# 4-PPS.net
KiCad netlist of a schematic drawn in Altium Designer
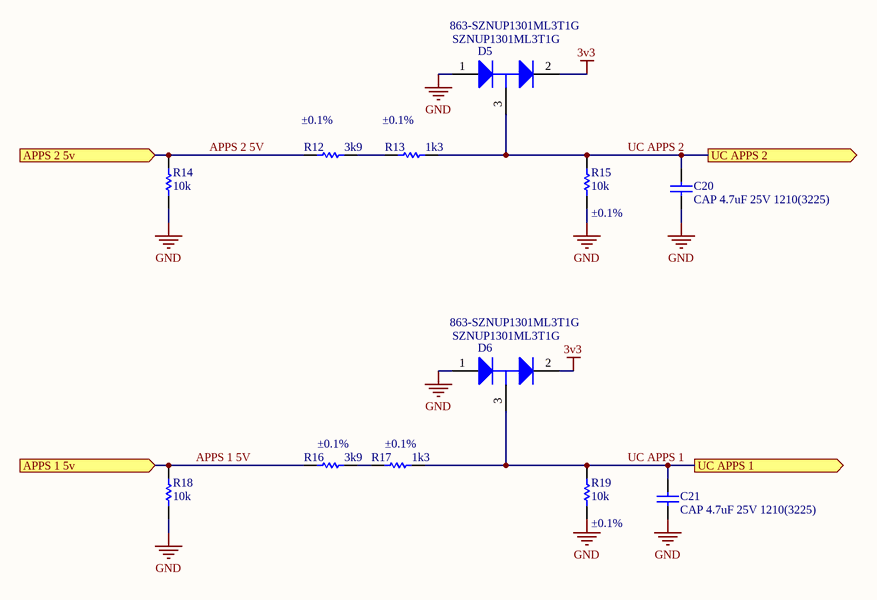
[diagram p0: 4-PPS.SchDoc]

(export (version "E")
  (design (tool "Eeschema 10.0.6"))
  (components
    (comp (ref "C20")
      (value "CAP 4.7uF 25V 1210(3225)")
      (footprint "CAPC1210(3225)220_M")
      (description "CAP 4.7uF 25V ±10% 1210 (3225 Metric) Thickness 2.2mm SMD")
      (fields (field (name "TOLERANCE") "Â±10%"))
      (libsource (lib "Altium Content Vault") (part "CAP"))
    )
    (comp (ref "C21")
      (value "CAP 4.7uF 25V 1210(3225)")
      (footprint "CAPC1210(3225)220_M")
      (description "CAP 4.7uF 25V ±10% 1210 (3225 Metric) Thickness 2.2mm SMD")
      (fields (field (name "TOLERANCE") "Â±10%"))
      (libsource (lib "Altium Content Vault") (part "CAP"))
    )
    (comp (ref "D5")
      (value "SZNUP1301ML3T1G")
      (footprint "ONSC-SOT-23-3-318-08_V")
      (fields
        (field (name "MANUFACTURER") "On Semiconductor")
        (field (name "SUPPLIER PART NUMBER 1") "863-SZNUP1301ML3T1G")
      )
      (libsource (lib "Altium Content Vault") (part "ONSC-NUP1301-SOT-23-3-318-08"))
    )
    (comp (ref "D6")
      (value "SZNUP1301ML3T1G")
      (footprint "ONSC-SOT-23-3-318-08_V")
      (fields
        (field (name "MANUFACTURER") "On Semiconductor")
        (field (name "SUPPLIER PART NUMBER 1") "863-SZNUP1301ML3T1G")
      )
      (libsource (lib "Altium Content Vault") (part "ONSC-NUP1301-SOT-23-3-318-08"))
    )
    (comp (ref "R12")
      (value "3k9")
      (footprint "1608[0603]")
      (description "Resistor")
      (fields
        (field (name "MANUFACTURER") "Yageo")
        (field (name "MANUFACTURER PART NUMBER") "RT0603BRD073K9L")
        (field (name "TOLERANCE") "±0.1%")
      )
      (libsource (lib "Miscellaneous Devices") (part "Res1"))
    )
    (comp (ref "R13")
      (value "1k3")
      (footprint "1608[0603]")
      (description "Resistor")
      (fields
        (field (name "MANUFACTURER") "Yageo")
        (field (name "MANUFACTURER PART NUMBER") "RT0603BRD071K3L")
        (field (name "TOLERANCE") "±0.1%")
      )
      (libsource (lib "Miscellaneous Devices") (part "Res1"))
    )
    (comp (ref "R14")
      (value "10k")
      (footprint "1608[0603]")
      (description "Resistor")
      (fields
        (field (name "MANUFACTURER") "Yageo")
        (field (name "MANUFACTURER PART NUMBER") "RC0603JR-0710KL")
      )
      (libsource (lib "Miscellaneous Devices") (part "Res1"))
    )
    (comp (ref "R15")
      (value "10k")
      (footprint "1608[0603]")
      (description "Resistor")
      (fields
        (field (name "MANUFACTURER") "Yageo")
        (field (name "MANUFACTURER PART NUMBER") "RT0603BRD0710KL")
        (field (name "TOLERANCE") "±0.1%")
      )
      (libsource (lib "Miscellaneous Devices") (part "Res1"))
    )
    (comp (ref "R16")
      (value "3k9")
      (footprint "1608[0603]")
      (description "Resistor")
      (fields
        (field (name "MANUFACTURER") "Yageo")
        (field (name "MANUFACTURER PART NUMBER") "RT0603BRD073K9L")
        (field (name "TOLERANCE") "±0.1%")
      )
      (libsource (lib "Miscellaneous Devices") (part "Res1"))
    )
    (comp (ref "R17")
      (value "1k3")
      (footprint "1608[0603]")
      (description "Resistor")
      (fields
        (field (name "MANUFACTURER") "Yageo")
        (field (name "MANUFACTURER PART NUMBER") "RT0603BRD071K3L")
        (field (name "TOLERANCE") "±0.1%")
      )
      (libsource (lib "Miscellaneous Devices") (part "Res1"))
    )
    (comp (ref "R18")
      (value "10k")
      (footprint "1608[0603]")
      (description "Resistor")
      (fields
        (field (name "MANUFACTURER") "Yageo")
        (field (name "MANUFACTURER PART NUMBER") "RC0603JR-0710KL")
      )
      (libsource (lib "Miscellaneous Devices") (part "Res1"))
    )
    (comp (ref "R19")
      (value "10k")
      (footprint "1608[0603]")
      (description "Resistor")
      (fields
        (field (name "MANUFACTURER") "Yageo")
        (field (name "MANUFACTURER PART NUMBER") "RT0603BRD0710KL")
        (field (name "TOLERANCE") "±0.1%")
      )
      (libsource (lib "Miscellaneous Devices") (part "Res1"))
    )
  )
  (nets
    (net (code "1") (name "/APPS 1 5V") (class "Default")
      (node (ref "R16") (pin "1") (pinfunction "1_1") (pintype "passive"))
      (node (ref "R18") (pin "2") (pinfunction "2_2") (pintype "passive"))
    )
    (net (code "2") (name "/APPS 2 5V") (class "Default")
      (node (ref "R12") (pin "1") (pinfunction "1_1") (pintype "passive"))
      (node (ref "R14") (pin "2") (pinfunction "2_2") (pintype "passive"))
    )
    (net (code "3") (name "/UC APPS 1") (class "Default")
      (node (ref "C21") (pin "2") (pinfunction "2_2") (pintype "passive"))
      (node (ref "D6") (pin "3") (pinfunction "K/A_3") (pintype "passive"))
      (node (ref "R17") (pin "2") (pinfunction "2_2") (pintype "passive"))
      (node (ref "R19") (pin "2") (pinfunction "2_2") (pintype "passive"))
    )
    (net (code "4") (name "/UC APPS 2") (class "Default")
      (node (ref "C20") (pin "2") (pinfunction "2_2") (pintype "passive"))
      (node (ref "D5") (pin "3") (pinfunction "K/A_3") (pintype "passive"))
      (node (ref "R13") (pin "2") (pinfunction "2_2") (pintype "passive"))
      (node (ref "R15") (pin "2") (pinfunction "2_2") (pintype "passive"))
    )
    (net (code "5") (name "3v3") (class "Default")
      (node (ref "D5") (pin "2") (pinfunction "K_2") (pintype "passive"))
      (node (ref "D6") (pin "2") (pinfunction "K_2") (pintype "passive"))
    )
    (net (code "6") (name "GND") (class "Default")
      (node (ref "C20") (pin "1") (pinfunction "1_1") (pintype "passive"))
      (node (ref "C21") (pin "1") (pinfunction "1_1") (pintype "passive"))
      (node (ref "D5") (pin "1") (pinfunction "A_1") (pintype "passive"))
      (node (ref "D6") (pin "1") (pinfunction "A_1") (pintype "passive"))
      (node (ref "R14") (pin "1") (pinfunction "1_1") (pintype "passive"))
      (node (ref "R15") (pin "1") (pinfunction "1_1") (pintype "passive"))
      (node (ref "R18") (pin "1") (pinfunction "1_1") (pintype "passive"))
      (node (ref "R19") (pin "1") (pinfunction "1_1") (pintype "passive"))
    )
    (net (code "7") (name "Net-(R12-Pad2)") (class "Default")
      (node (ref "R12") (pin "2") (pinfunction "2_2") (pintype "passive"))
      (node (ref "R13") (pin "1") (pinfunction "1_1") (pintype "passive"))
    )
    (net (code "8") (name "Net-(R16-Pad2)") (class "Default")
      (node (ref "R16") (pin "2") (pinfunction "2_2") (pintype "passive"))
      (node (ref "R17") (pin "1") (pinfunction "1_1") (pintype "passive"))
    )
  )
)
